# robohand.net
KiCad netlist of a schematic drawn in EAGLE
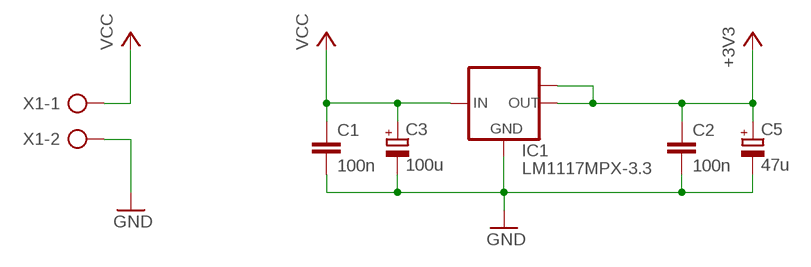
[diagram p0: schematic, sheet 1]
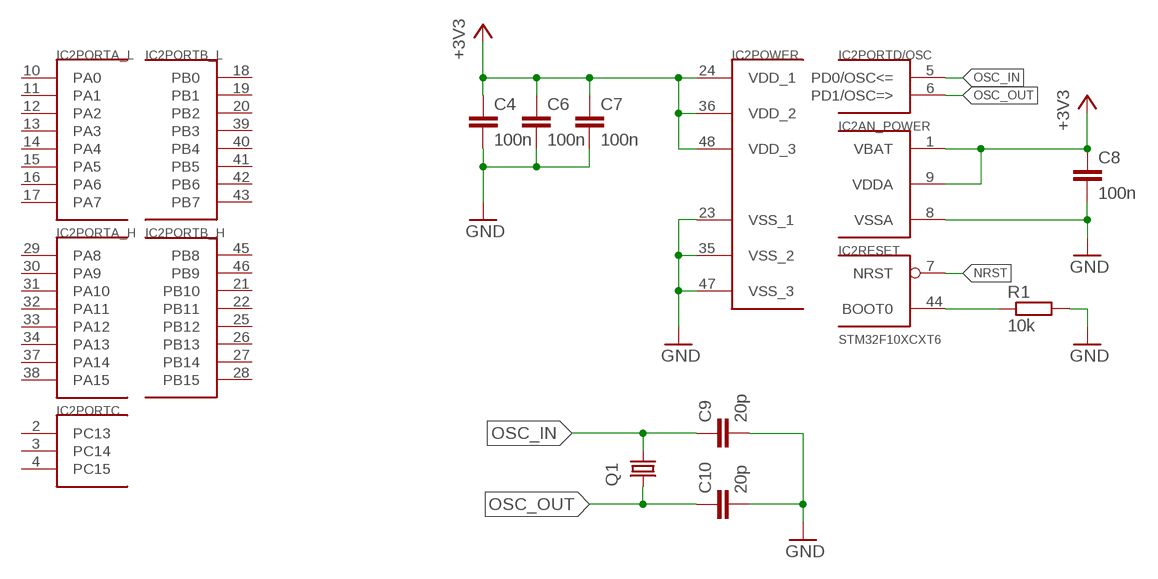
[diagram p1: schematic, sheet 2]
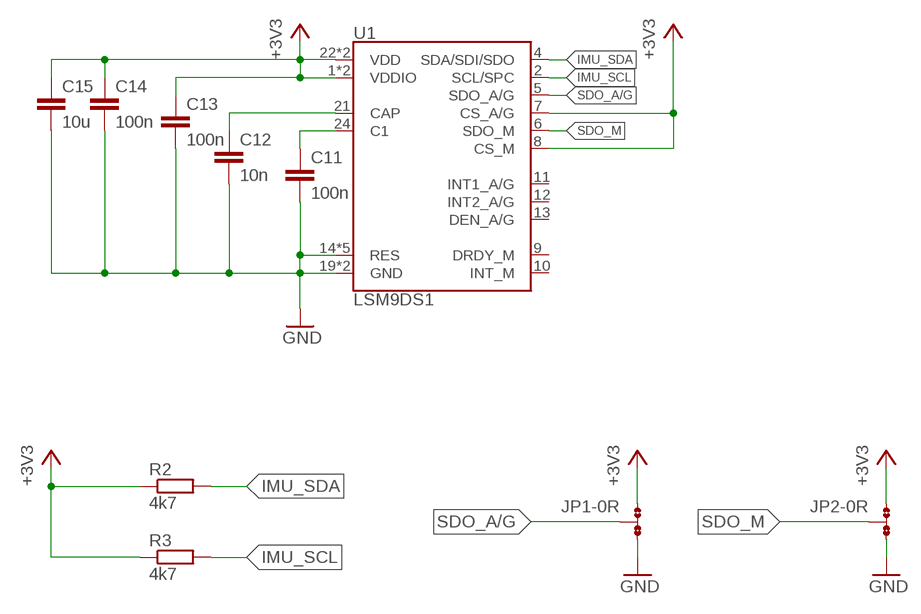
[diagram p2: schematic, sheet 3]
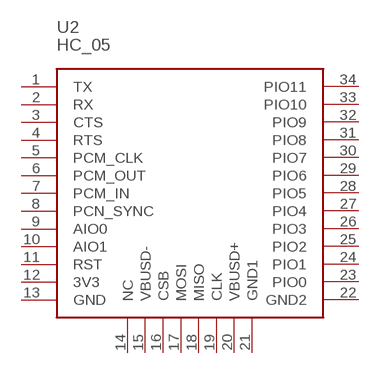
[diagram p3: schematic, sheet 4]
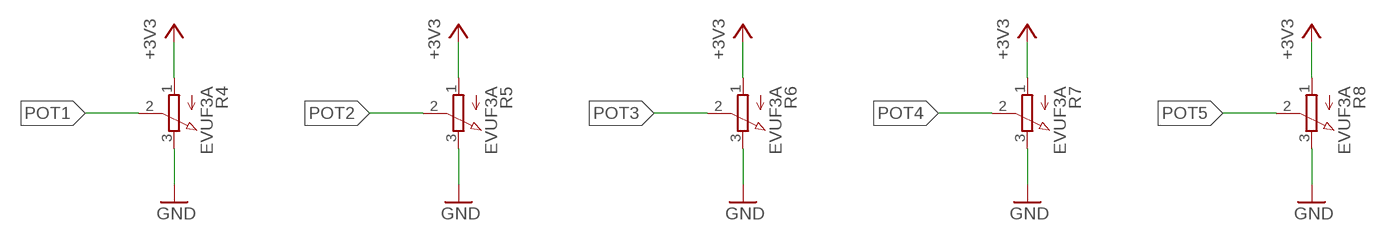
[diagram p4: schematic, sheet 5]

(export (version "E")
  (design (tool "Eeschema 10.0.6"))
  (components
    (comp (ref "C4")
      (value "100n")
      (footprint "eagle-import:C0805")
      (libsource (lib "eagle-import") (part "C-EUC0805"))
    )
    (comp (ref "C6")
      (value "100n")
      (footprint "eagle-import:C0805")
      (libsource (lib "eagle-import") (part "C-EUC0805"))
    )
    (comp (ref "C7")
      (value "100n")
      (footprint "eagle-import:C0805")
      (libsource (lib "eagle-import") (part "C-EUC0805"))
    )
    (comp (ref "C8")
      (value "100n")
      (footprint "eagle-import:C0805")
      (libsource (lib "eagle-import") (part "C-EUC0805"))
    )
    (comp (ref "C9")
      (value "20p")
      (footprint "eagle-import:C0805")
      (libsource (lib "eagle-import") (part "C-EUC0805"))
    )
    (comp (ref "C10")
      (value "20p")
      (footprint "eagle-import:C0805")
      (libsource (lib "eagle-import") (part "C-EUC0805"))
    )
    (comp (ref "IC2")
      (value "STM32F10XCXT6")
      (footprint "eagle-import:TQFP48")
      (libsource (lib "eagle-import") (part "STM32F10XCXT6"))
    )
    (comp (ref "Q1")
      (value "CRYSTALCTS406")
      (footprint "eagle-import:CTS406")
      (libsource (lib "eagle-import") (part "CRYSTALCTS406"))
    )
    (comp (ref "R1")
      (value "10k")
      (footprint "eagle-import:R0805")
      (libsource (lib "eagle-import") (part "R-EU_R0805"))
    )
    (comp (ref "U2")
      (value "HC_05")
      (footprint "eagle-import:BLUETOOTH_SMD")
      (libsource (lib "eagle-import") (part "HC_05"))
    )
    (comp (ref "C1")
      (value "100n")
      (footprint "eagle-import:C0805")
      (libsource (lib "eagle-import") (part "C-EUC0805"))
    )
    (comp (ref "C2")
      (value "100n")
      (footprint "eagle-import:C0805")
      (libsource (lib "eagle-import") (part "C-EUC0805"))
    )
    (comp (ref "C3")
      (value "100u")
      (footprint "eagle-import:CT7343")
      (libsource (lib "eagle-import") (part "CPOL-EUCT7343"))
    )
    (comp (ref "C5")
      (value "47u")
      (footprint "eagle-import:CT3528")
      (libsource (lib "eagle-import") (part "CPOL-EUCT3528"))
    )
    (comp (ref "IC1")
      (value "LM1117MPX-3.3")
      (footprint "eagle-import:SOT223")
      (libsource (lib "eagle-import") (part "LM1117MPX-3.3"))
    )
    (comp (ref "X1")
      (value "AK500/2")
      (footprint "eagle-import:AK500_2")
      (libsource (lib "eagle-import") (part "AK500/2"))
    )
    (comp (ref "R4")
      (value "EVUF3A")
      (footprint "eagle-import:EVUF")
      (libsource (lib "eagle-import") (part "EVUAF3"))
    )
    (comp (ref "R5")
      (value "EVUF3A")
      (footprint "eagle-import:EVUF")
      (libsource (lib "eagle-import") (part "EVUAF3"))
    )
    (comp (ref "R6")
      (value "EVUF3A")
      (footprint "eagle-import:EVUF")
      (libsource (lib "eagle-import") (part "EVUAF3"))
    )
    (comp (ref "R7")
      (value "EVUF3A")
      (footprint "eagle-import:EVUF")
      (libsource (lib "eagle-import") (part "EVUAF3"))
    )
    (comp (ref "R8")
      (value "EVUF3A")
      (footprint "eagle-import:EVUF")
      (libsource (lib "eagle-import") (part "EVUAF3"))
    )
    (comp (ref "C11")
      (value "100n")
      (footprint "eagle-import:C0805")
      (libsource (lib "eagle-import") (part "C-EUC0805"))
    )
    (comp (ref "C12")
      (value "10n")
      (footprint "eagle-import:C0805")
      (libsource (lib "eagle-import") (part "C-EUC0805"))
    )
    (comp (ref "C13")
      (value "100n")
      (footprint "eagle-import:C0805")
      (libsource (lib "eagle-import") (part "C-EUC0805"))
    )
    (comp (ref "C14")
      (value "100n")
      (footprint "eagle-import:C0805")
      (libsource (lib "eagle-import") (part "C-EUC0805"))
    )
    (comp (ref "C15")
      (value "10u")
      (footprint "eagle-import:C0805")
      (libsource (lib "eagle-import") (part "C-EUC0805"))
    )
    (comp (ref "JP1")
      (value "0R-JUMPA")
      (footprint "eagle-import:A0R-JMP")
      (libsource (lib "eagle-import") (part "0R-JUMPA"))
    )
    (comp (ref "JP2")
      (value "0R-JUMPA")
      (footprint "eagle-import:A0R-JMP")
      (libsource (lib "eagle-import") (part "0R-JUMPA"))
    )
    (comp (ref "R2")
      (value "4k7")
      (footprint "eagle-import:R0805")
      (libsource (lib "eagle-import") (part "R-EU_R0805"))
    )
    (comp (ref "R3")
      (value "4k7")
      (footprint "eagle-import:R0805")
      (libsource (lib "eagle-import") (part "R-EU_R0805"))
    )
    (comp (ref "U1")
      (value "LSM9DS1")
      (footprint "eagle-import:LGA24-8X4")
      (libsource (lib "eagle-import") (part "LSM9DS1"))
    )
  )
  (nets
    (net (code "1") (name "+3V3") (class "Default")
      (node (ref "C13") (pin "1") (pinfunction "1_1") (pintype "passive"))
      (node (ref "C14") (pin "1") (pinfunction "1_1") (pintype "passive"))
      (node (ref "C15") (pin "1") (pinfunction "1_1") (pintype "passive"))
      (node (ref "C2") (pin "1") (pinfunction "1_1") (pintype "passive"))
      (node (ref "C4") (pin "1") (pinfunction "1_1") (pintype "passive"))
      (node (ref "C5") (pin "+") (pinfunction "+_+") (pintype "passive"))
      (node (ref "C6") (pin "1") (pinfunction "1_1") (pintype "passive"))
      (node (ref "C7") (pin "1") (pinfunction "1_1") (pintype "passive"))
      (node (ref "C8") (pin "1") (pinfunction "1_1") (pintype "passive"))
      (node (ref "IC1") (pin "2") (pinfunction "OUT_2") (pintype "passive"))
      (node (ref "IC1") (pin "TAB") (pinfunction "OUT1_TAB") (pintype "passive"))
      (node (ref "IC2") (pin "1") (pinfunction "VBAT_1") (pintype "power_in"))
      (node (ref "IC2") (pin "24") (pinfunction "VDD_1_24") (pintype "power_in"))
      (node (ref "IC2") (pin "36") (pinfunction "VDD_2_36") (pintype "power_in"))
      (node (ref "IC2") (pin "48") (pinfunction "VDD_3_48") (pintype "power_in"))
      (node (ref "IC2") (pin "9") (pinfunction "VDDA_9") (pintype "power_in"))
      (node (ref "JP1") (pin "1") (pinfunction "1_1") (pintype "passive"))
      (node (ref "JP2") (pin "1") (pinfunction "1_1") (pintype "passive"))
      (node (ref "R2") (pin "1") (pinfunction "1_1") (pintype "passive"))
      (node (ref "R3") (pin "1") (pinfunction "1_1") (pintype "passive"))
      (node (ref "R4") (pin "1") (pinfunction "A_1") (pintype "passive"))
      (node (ref "R5") (pin "1") (pinfunction "A_1") (pintype "passive"))
      (node (ref "R6") (pin "1") (pinfunction "A_1") (pintype "passive"))
      (node (ref "R7") (pin "1") (pinfunction "A_1") (pintype "passive"))
      (node (ref "R8") (pin "1") (pinfunction "A_1") (pintype "passive"))
      (node (ref "U1") (pin "1") (pinfunction "VDDIO_1") (pintype "bidirectional"))
      (node (ref "U1") (pin "22") (pinfunction "VDD_22") (pintype "bidirectional"))
      (node (ref "U1") (pin "23") (pinfunction "VDD_23") (pintype "bidirectional"))
      (node (ref "U1") (pin "3") (pinfunction "VDDIO_3") (pintype "bidirectional"))
      (node (ref "U1") (pin "7") (pinfunction "CS_A/G_7") (pintype "bidirectional"))
      (node (ref "U1") (pin "8") (pinfunction "CS_M_8") (pintype "bidirectional"))
    )
    (net (code "2") (name "GND") (class "Default")
      (node (ref "C1") (pin "2") (pinfunction "2_2") (pintype "passive"))
      (node (ref "C10") (pin "2") (pinfunction "2_2") (pintype "passive"))
      (node (ref "C11") (pin "2") (pinfunction "2_2") (pintype "passive"))
      (node (ref "C12") (pin "2") (pinfunction "2_2") (pintype "passive"))
      (node (ref "C13") (pin "2") (pinfunction "2_2") (pintype "passive"))
      (node (ref "C14") (pin "2") (pinfunction "2_2") (pintype "passive"))
      (node (ref "C15") (pin "2") (pinfunction "2_2") (pintype "passive"))
      (node (ref "C2") (pin "2") (pinfunction "2_2") (pintype "passive"))
      (node (ref "C3") (pin "-") (pinfunction "-_-") (pintype "passive"))
      (node (ref "C4") (pin "2") (pinfunction "2_2") (pintype "passive"))
      (node (ref "C5") (pin "-") (pinfunction "-_-") (pintype "passive"))
      (node (ref "C6") (pin "2") (pinfunction "2_2") (pintype "passive"))
      (node (ref "C7") (pin "2") (pinfunction "2_2") (pintype "passive"))
      (node (ref "C8") (pin "2") (pinfunction "2_2") (pintype "passive"))
      (node (ref "C9") (pin "2") (pinfunction "2_2") (pintype "passive"))
      (node (ref "IC1") (pin "1") (pinfunction "GND_1") (pintype "input"))
      (node (ref "IC2") (pin "23") (pinfunction "VSS_1_23") (pintype "power_in"))
      (node (ref "IC2") (pin "35") (pinfunction "VSS_2_35") (pintype "power_in"))
      (node (ref "IC2") (pin "47") (pinfunction "VSS_3_47") (pintype "power_in"))
      (node (ref "IC2") (pin "8") (pinfunction "VSSA_8") (pintype "power_in"))
      (node (ref "JP1") (pin "3") (pinfunction "3_3") (pintype "passive"))
      (node (ref "JP2") (pin "3") (pinfunction "3_3") (pintype "passive"))
      (node (ref "R1") (pin "2") (pinfunction "2_2") (pintype "passive"))
      (node (ref "R4") (pin "3") (pinfunction "E_3") (pintype "passive"))
      (node (ref "R5") (pin "3") (pinfunction "E_3") (pintype "passive"))
      (node (ref "R6") (pin "3") (pinfunction "E_3") (pintype "passive"))
      (node (ref "R7") (pin "3") (pinfunction "E_3") (pintype "passive"))
      (node (ref "R8") (pin "3") (pinfunction "E_3") (pintype "passive"))
      (node (ref "U1") (pin "14") (pinfunction "RES_14") (pintype "bidirectional"))
      (node (ref "U1") (pin "15") (pinfunction "RES_15") (pintype "bidirectional"))
      (node (ref "U1") (pin "16") (pinfunction "RES_16") (pintype "bidirectional"))
      (node (ref "U1") (pin "17") (pinfunction "RES_17") (pintype "bidirectional"))
      (node (ref "U1") (pin "18") (pinfunction "RES_18") (pintype "bidirectional"))
      (node (ref "U1") (pin "19") (pinfunction "GND_19") (pintype "bidirectional"))
      (node (ref "U1") (pin "20") (pinfunction "GND_20") (pintype "bidirectional"))
      (node (ref "X1") (pin "2") (pinfunction "KL_2") (pintype "passive"))
    )
    (net (code "3") (name "IMU_SCL") (class "Default")
      (node (ref "R3") (pin "2") (pinfunction "2_2") (pintype "passive"))
      (node (ref "U1") (pin "2") (pinfunction "SCL/SPC_2") (pintype "bidirectional"))
    )
    (net (code "4") (name "IMU_SDA") (class "Default")
      (node (ref "R2") (pin "2") (pinfunction "2_2") (pintype "passive"))
      (node (ref "U1") (pin "4") (pinfunction "SDA/SDI/SDO_4") (pintype "bidirectional"))
    )
    (net (code "5") (name "NRST") (class "Default")
      (node (ref "IC2") (pin "7") (pinfunction "NRST_7") (pintype "input"))
    )
    (net (code "6") (name "Net-(IC2I-BOOT0)") (class "Default")
      (node (ref "IC2") (pin "44") (pinfunction "BOOT0_44") (pintype "input"))
      (node (ref "R1") (pin "1") (pinfunction "1_1") (pintype "passive"))
    )
    (net (code "7") (name "Net-(U1-C1)") (class "Default")
      (node (ref "C11") (pin "1") (pinfunction "1_1") (pintype "passive"))
      (node (ref "U1") (pin "24") (pinfunction "C1_24") (pintype "bidirectional"))
    )
    (net (code "8") (name "Net-(U1-CAP)") (class "Default")
      (node (ref "C12") (pin "1") (pinfunction "1_1") (pintype "passive"))
      (node (ref "U1") (pin "21") (pinfunction "CAP_21") (pintype "bidirectional"))
    )
    (net (code "9") (name "OSC_IN") (class "Default")
      (node (ref "C9") (pin "1") (pinfunction "1_1") (pintype "passive"))
      (node (ref "IC2") (pin "5") (pinfunction "PD0/OSC<=_5") (pintype "bidirectional"))
      (node (ref "Q1") (pin "1") (pinfunction "1_1") (pintype "passive"))
    )
    (net (code "10") (name "OSC_OUT") (class "Default")
      (node (ref "C10") (pin "1") (pinfunction "1_1") (pintype "passive"))
      (node (ref "IC2") (pin "6") (pinfunction "PD1/OSC=>_6") (pintype "bidirectional"))
      (node (ref "Q1") (pin "3") (pinfunction "2_3") (pintype "passive"))
    )
    (net (code "11") (name "POT1") (class "Default")
      (node (ref "R4") (pin "2") (pinfunction "S_2") (pintype "passive"))
    )
    (net (code "12") (name "POT2") (class "Default")
      (node (ref "R5") (pin "2") (pinfunction "S_2") (pintype "passive"))
    )
    (net (code "13") (name "POT3") (class "Default")
      (node (ref "R6") (pin "2") (pinfunction "S_2") (pintype "passive"))
    )
    (net (code "14") (name "POT4") (class "Default")
      (node (ref "R7") (pin "2") (pinfunction "S_2") (pintype "passive"))
    )
    (net (code "15") (name "POT5") (class "Default")
      (node (ref "R8") (pin "2") (pinfunction "S_2") (pintype "passive"))
    )
    (net (code "16") (name "SDO_A{slash}G") (class "Default")
      (node (ref "JP1") (pin "2") (pinfunction "2_2") (pintype "passive"))
      (node (ref "U1") (pin "5") (pinfunction "SDO_A/G_5") (pintype "bidirectional"))
    )
    (net (code "17") (name "SDO_M") (class "Default")
      (node (ref "JP2") (pin "2") (pinfunction "2_2") (pintype "passive"))
      (node (ref "U1") (pin "6") (pinfunction "SDO_M_6") (pintype "bidirectional"))
    )
    (net (code "18") (name "VCC") (class "Default")
      (node (ref "C1") (pin "1") (pinfunction "1_1") (pintype "passive"))
      (node (ref "C3") (pin "+") (pinfunction "+_+") (pintype "passive"))
      (node (ref "IC1") (pin "3") (pinfunction "IN_3") (pintype "input"))
      (node (ref "X1") (pin "1") (pinfunction "KL_1") (pintype "passive"))
    )
    (net (code "19") (name "unconnected-(IC2B-PA8-Pad29)") (class "Default")
      (node (ref "IC2") (pin "29") (pinfunction "PA8_29") (pintype "bidirectional"))
    )
    (net (code "20") (name "unconnected-(IC2B-PA9-Pad30)") (class "Default")
      (node (ref "IC2") (pin "30") (pinfunction "PA9_30") (pintype "bidirectional"))
    )
    (net (code "21") (name "unconnected-(IC2B-PA10-Pad31)") (class "Default")
      (node (ref "IC2") (pin "31") (pinfunction "PA10_31") (pintype "bidirectional"))
    )
    (net (code "22") (name "unconnected-(IC2B-PA11-Pad32)") (class "Default")
      (node (ref "IC2") (pin "32") (pinfunction "PA11_32") (pintype "bidirectional"))
    )
    (net (code "23") (name "unconnected-(IC2B-PA12-Pad33)") (class "Default")
      (node (ref "IC2") (pin "33") (pinfunction "PA12_33") (pintype "bidirectional"))
    )
    (net (code "24") (name "unconnected-(IC2B-PA13-Pad34)") (class "Default")
      (node (ref "IC2") (pin "34") (pinfunction "PA13_34") (pintype "bidirectional"))
    )
    (net (code "25") (name "unconnected-(IC2B-PA14-Pad37)") (class "Default")
      (node (ref "IC2") (pin "37") (pinfunction "PA14_37") (pintype "bidirectional"))
    )
    (net (code "26") (name "unconnected-(IC2B-PA15-Pad38)") (class "Default")
      (node (ref "IC2") (pin "38") (pinfunction "PA15_38") (pintype "bidirectional"))
    )
    (net (code "27") (name "unconnected-(IC2C-PA0-Pad10)") (class "Default")
      (node (ref "IC2") (pin "10") (pinfunction "PA0_10") (pintype "bidirectional"))
    )
    (net (code "28") (name "unconnected-(IC2C-PA1-Pad11)") (class "Default")
      (node (ref "IC2") (pin "11") (pinfunction "PA1_11") (pintype "bidirectional"))
    )
    (net (code "29") (name "unconnected-(IC2C-PA2-Pad12)") (class "Default")
      (node (ref "IC2") (pin "12") (pinfunction "PA2_12") (pintype "bidirectional"))
    )
    (net (code "30") (name "unconnected-(IC2C-PA3-Pad13)") (class "Default")
      (node (ref "IC2") (pin "13") (pinfunction "PA3_13") (pintype "bidirectional"))
    )
    (net (code "31") (name "unconnected-(IC2C-PA4-Pad14)") (class "Default")
      (node (ref "IC2") (pin "14") (pinfunction "PA4_14") (pintype "bidirectional"))
    )
    (net (code "32") (name "unconnected-(IC2C-PA5-Pad15)") (class "Default")
      (node (ref "IC2") (pin "15") (pinfunction "PA5_15") (pintype "bidirectional"))
    )
    (net (code "33") (name "unconnected-(IC2C-PA6-Pad16)") (class "Default")
      (node (ref "IC2") (pin "16") (pinfunction "PA6_16") (pintype "bidirectional"))
    )
    (net (code "34") (name "unconnected-(IC2C-PA7-Pad17)") (class "Default")
      (node (ref "IC2") (pin "17") (pinfunction "PA7_17") (pintype "bidirectional"))
    )
    (net (code "35") (name "unconnected-(IC2D-PB8-Pad45)") (class "Default")
      (node (ref "IC2") (pin "45") (pinfunction "PB8_45") (pintype "bidirectional"))
    )
    (net (code "36") (name "unconnected-(IC2D-PB9-Pad46)") (class "Default")
      (node (ref "IC2") (pin "46") (pinfunction "PB9_46") (pintype "bidirectional"))
    )
    (net (code "37") (name "unconnected-(IC2D-PB10-Pad21)") (class "Default")
      (node (ref "IC2") (pin "21") (pinfunction "PB10_21") (pintype "bidirectional"))
    )
    (net (code "38") (name "unconnected-(IC2D-PB11-Pad22)") (class "Default")
      (node (ref "IC2") (pin "22") (pinfunction "PB11_22") (pintype "bidirectional"))
    )
    (net (code "39") (name "unconnected-(IC2D-PB12-Pad25)") (class "Default")
      (node (ref "IC2") (pin "25") (pinfunction "PB12_25") (pintype "bidirectional"))
    )
    (net (code "40") (name "unconnected-(IC2D-PB13-Pad26)") (class "Default")
      (node (ref "IC2") (pin "26") (pinfunction "PB13_26") (pintype "bidirectional"))
    )
    (net (code "41") (name "unconnected-(IC2D-PB14-Pad27)") (class "Default")
      (node (ref "IC2") (pin "27") (pinfunction "PB14_27") (pintype "bidirectional"))
    )
    (net (code "42") (name "unconnected-(IC2D-PB15-Pad28)") (class "Default")
      (node (ref "IC2") (pin "28") (pinfunction "PB15_28") (pintype "bidirectional"))
    )
    (net (code "43") (name "unconnected-(IC2E-PB0-Pad18)") (class "Default")
      (node (ref "IC2") (pin "18") (pinfunction "PB0_18") (pintype "bidirectional"))
    )
    (net (code "44") (name "unconnected-(IC2E-PB1-Pad19)") (class "Default")
      (node (ref "IC2") (pin "19") (pinfunction "PB1_19") (pintype "bidirectional"))
    )
    (net (code "45") (name "unconnected-(IC2E-PB2-Pad20)") (class "Default")
      (node (ref "IC2") (pin "20") (pinfunction "PB2_20") (pintype "bidirectional"))
    )
    (net (code "46") (name "unconnected-(IC2E-PB3-Pad39)") (class "Default")
      (node (ref "IC2") (pin "39") (pinfunction "PB3_39") (pintype "bidirectional"))
    )
    (net (code "47") (name "unconnected-(IC2E-PB4-Pad40)") (class "Default")
      (node (ref "IC2") (pin "40") (pinfunction "PB4_40") (pintype "bidirectional"))
    )
    (net (code "48") (name "unconnected-(IC2E-PB5-Pad41)") (class "Default")
      (node (ref "IC2") (pin "41") (pinfunction "PB5_41") (pintype "bidirectional"))
    )
    (net (code "49") (name "unconnected-(IC2E-PB6-Pad42)") (class "Default")
      (node (ref "IC2") (pin "42") (pinfunction "PB6_42") (pintype "bidirectional"))
    )
    (net (code "50") (name "unconnected-(IC2E-PB7-Pad43)") (class "Default")
      (node (ref "IC2") (pin "43") (pinfunction "PB7_43") (pintype "bidirectional"))
    )
    (net (code "51") (name "unconnected-(IC2F-PC13-Pad2)") (class "Default")
      (node (ref "IC2") (pin "2") (pinfunction "PC13_2") (pintype "bidirectional"))
    )
    (net (code "52") (name "unconnected-(IC2F-PC14-Pad3)") (class "Default")
      (node (ref "IC2") (pin "3") (pinfunction "PC14_3") (pintype "bidirectional"))
    )
    (net (code "53") (name "unconnected-(IC2F-PC15-Pad4)") (class "Default")
      (node (ref "IC2") (pin "4") (pinfunction "PC15_4") (pintype "bidirectional"))
    )
    (net (code "54") (name "unconnected-(U1-DEN_A{slash}G-Pad13)") (class "Default")
      (node (ref "U1") (pin "13") (pinfunction "DEN_A/G_13") (pintype "bidirectional"))
    )
    (net (code "55") (name "unconnected-(U1-DRDY_M-Pad9)") (class "Default")
      (node (ref "U1") (pin "9") (pinfunction "DRDY_M_9") (pintype "bidirectional"))
    )
    (net (code "56") (name "unconnected-(U1-INT1_A{slash}G-Pad11)") (class "Default")
      (node (ref "U1") (pin "11") (pinfunction "INT1_A/G_11") (pintype "bidirectional"))
    )
    (net (code "57") (name "unconnected-(U1-INT2_A{slash}G-Pad12)") (class "Default")
      (node (ref "U1") (pin "12") (pinfunction "INT2_A/G_12") (pintype "bidirectional"))
    )
    (net (code "58") (name "unconnected-(U1-INT_M-Pad10)") (class "Default")
      (node (ref "U1") (pin "10") (pinfunction "INT_M_10") (pintype "bidirectional"))
    )
    (net (code "59") (name "unconnected-(U2-3V3-Pad12)") (class "Default")
      (node (ref "U2") (pin "12") (pinfunction "3V3_12") (pintype "bidirectional"))
    )
    (net (code "60") (name "unconnected-(U2-AIO0-Pad9)") (class "Default")
      (node (ref "U2") (pin "9") (pinfunction "AIO0_9") (pintype "bidirectional"))
    )
    (net (code "61") (name "unconnected-(U2-AIO1-Pad10)") (class "Default")
      (node (ref "U2") (pin "10") (pinfunction "AIO1_10") (pintype "bidirectional"))
    )
    (net (code "62") (name "unconnected-(U2-CLK-Pad19)") (class "Default")
      (node (ref "U2") (pin "19") (pinfunction "CLK_19") (pintype "bidirectional"))
    )
    (net (code "63") (name "unconnected-(U2-CSB-Pad16)") (class "Default")
      (node (ref "U2") (pin "16") (pinfunction "CSB_16") (pintype "bidirectional"))
    )
    (net (code "64") (name "unconnected-(U2-CTS-Pad3)") (class "Default")
      (node (ref "U2") (pin "3") (pinfunction "CTS_3") (pintype "bidirectional"))
    )
    (net (code "65") (name "unconnected-(U2-GND-Pad13)") (class "Default")
      (node (ref "U2") (pin "13") (pinfunction "GND_13") (pintype "bidirectional"))
    )
    (net (code "66") (name "unconnected-(U2-GND1-Pad21)") (class "Default")
      (node (ref "U2") (pin "21") (pinfunction "GND1_21") (pintype "bidirectional"))
    )
    (net (code "67") (name "unconnected-(U2-GND2-Pad22)") (class "Default")
      (node (ref "U2") (pin "22") (pinfunction "GND2_22") (pintype "bidirectional"))
    )
    (net (code "68") (name "unconnected-(U2-MISO-Pad18)") (class "Default")
      (node (ref "U2") (pin "18") (pinfunction "MISO_18") (pintype "bidirectional"))
    )
    (net (code "69") (name "unconnected-(U2-MOSI-Pad17)") (class "Default")
      (node (ref "U2") (pin "17") (pinfunction "MOSI_17") (pintype "bidirectional"))
    )
    (net (code "70") (name "unconnected-(U2-NC-Pad14)") (class "Default")
      (node (ref "U2") (pin "14") (pinfunction "NC_14") (pintype "bidirectional"))
    )
    (net (code "71") (name "unconnected-(U2-PCM_CLK-Pad5)") (class "Default")
      (node (ref "U2") (pin "5") (pinfunction "PCM_CLK_5") (pintype "bidirectional"))
    )
    (net (code "72") (name "unconnected-(U2-PCM_IN-Pad7)") (class "Default")
      (node (ref "U2") (pin "7") (pinfunction "PCM_IN_7") (pintype "bidirectional"))
    )
    (net (code "73") (name "unconnected-(U2-PCM_OUT-Pad6)") (class "Default")
      (node (ref "U2") (pin "6") (pinfunction "PCM_OUT_6") (pintype "bidirectional"))
    )
    (net (code "74") (name "unconnected-(U2-PCN_SYNC-Pad8)") (class "Default")
      (node (ref "U2") (pin "8") (pinfunction "PCN_SYNC_8") (pintype "bidirectional"))
    )
    (net (code "75") (name "unconnected-(U2-PIO0-Pad23)") (class "Default")
      (node (ref "U2") (pin "23") (pinfunction "PIO0_23") (pintype "bidirectional"))
    )
    (net (code "76") (name "unconnected-(U2-PIO1-Pad24)") (class "Default")
      (node (ref "U2") (pin "24") (pinfunction "PIO1_24") (pintype "bidirectional"))
    )
    (net (code "77") (name "unconnected-(U2-PIO2-Pad25)") (class "Default")
      (node (ref "U2") (pin "25") (pinfunction "PIO2_25") (pintype "bidirectional"))
    )
    (net (code "78") (name "unconnected-(U2-PIO3-Pad26)") (class "Default")
      (node (ref "U2") (pin "26") (pinfunction "PIO3_26") (pintype "bidirectional"))
    )
    (net (code "79") (name "unconnected-(U2-PIO4-Pad27)") (class "Default")
      (node (ref "U2") (pin "27") (pinfunction "PIO4_27") (pintype "bidirectional"))
    )
    (net (code "80") (name "unconnected-(U2-PIO5-Pad28)") (class "Default")
      (node (ref "U2") (pin "28") (pinfunction "PIO5_28") (pintype "bidirectional"))
    )
    (net (code "81") (name "unconnected-(U2-PIO6-Pad29)") (class "Default")
      (node (ref "U2") (pin "29") (pinfunction "PIO6_29") (pintype "bidirectional"))
    )
    (net (code "82") (name "unconnected-(U2-PIO7-Pad30)") (class "Default")
      (node (ref "U2") (pin "30") (pinfunction "PIO7_30") (pintype "bidirectional"))
    )
    (net (code "83") (name "unconnected-(U2-PIO8-Pad31)") (class "Default")
      (node (ref "U2") (pin "31") (pinfunction "PIO8_31") (pintype "bidirectional"))
    )
    (net (code "84") (name "unconnected-(U2-PIO9-Pad32)") (class "Default")
      (node (ref "U2") (pin "32") (pinfunction "PIO9_32") (pintype "bidirectional"))
    )
    (net (code "85") (name "unconnected-(U2-PIO10-Pad33)") (class "Default")
      (node (ref "U2") (pin "33") (pinfunction "PIO10_33") (pintype "bidirectional"))
    )
    (net (code "86") (name "unconnected-(U2-PIO11-Pad34)") (class "Default")
      (node (ref "U2") (pin "34") (pinfunction "PIO11_34") (pintype "bidirectional"))
    )
    (net (code "87") (name "unconnected-(U2-RST-Pad11)") (class "Default")
      (node (ref "U2") (pin "11") (pinfunction "RST_11") (pintype "bidirectional"))
    )
    (net (code "88") (name "unconnected-(U2-RTS-Pad4)") (class "Default")
      (node (ref "U2") (pin "4") (pinfunction "RTS_4") (pintype "bidirectional"))
    )
    (net (code "89") (name "unconnected-(U2-RX-Pad2)") (class "Default")
      (node (ref "U2") (pin "2") (pinfunction "RX_2") (pintype "bidirectional"))
    )
    (net (code "90") (name "unconnected-(U2-TX-Pad1)") (class "Default")
      (node (ref "U2") (pin "1") (pinfunction "TX_1") (pintype "bidirectional"))
    )
    (net (code "91") (name "unconnected-(U2-VBUSD+-Pad20)") (class "Default")
      (node (ref "U2") (pin "20") (pinfunction "VBUSD+_20") (pintype "bidirectional"))
    )
    (net (code "92") (name "unconnected-(U2-VBUSD--Pad15)") (class "Default")
      (node (ref "U2") (pin "15") (pinfunction "VBUSD-_15") (pintype "bidirectional"))
    )
  )
)
